# BUCK_CONVERTER_SCHEMAT_C.net
KiCad netlist of a schematic drawn in Altium Designer
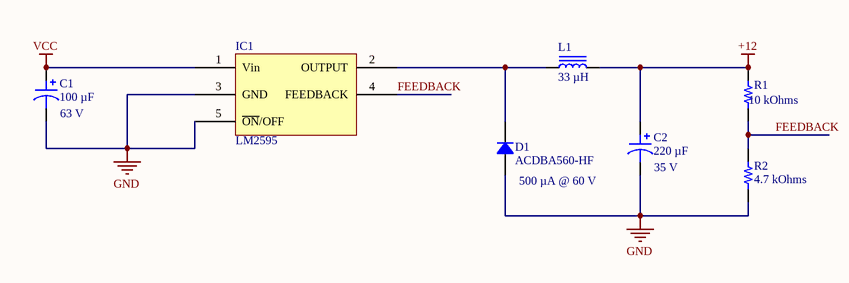
[diagram p0: BUCK CONVERTER SCHEMATİC.SchDoc]

(export (version "E")
  (design (tool "Eeschema 10.0.6"))
  (components
    (comp (ref "C1")
      (value "100 µF")
      (footprint "CAP AL TH D8 L3.5 H12.5")
      (description "CAP ALUM 100UF 20% 63V RADIAL")
      (fields
        (field (name "PART NUMBER") "ECA-1JM101")
        (field (name "MANUFACTURER") "Panasonic Electronic Components")
        (field (name "VOLTAGE - RATED") "63 V")
      )
      (libsource (lib "Celestial Altium Library - altium_library") (part "Polarised Capacitor"))
    )
    (comp (ref "C2")
      (value "220 µF")
      (footprint "CAP AL TH D8 L3.5 H12.5")
      (description "CAP ALUM 220UF 20% 35V RADIAL")
      (fields
        (field (name "PART NUMBER") "ECA-1VM221")
        (field (name "MANUFACTURER") "Panasonic Electronic Components")
        (field (name "VOLTAGE - RATED") "35 V")
      )
      (libsource (lib "Celestial Altium Library - altium_library") (part "Polarised Capacitor"))
    )
    (comp (ref "D1")
      (value "ACDBA560-HF")
      (footprint "DO214AC SMA")
      (description "DIODE SCHOTTKY 60V 5A DO214AC")
      (fields
        (field (name "CURRENT - REVERSE LEAKAGE @ VR") "500 µA @ 60 V")
        (field (name "MANUFACTURER") "Comchip Technology")
      )
      (libsource (lib "Celestial Altium Library - altium_library") (part "Diode"))
    )
    (comp (ref "IC1")
      (value "LM2595")
      (footprint "LM2596 FOOTPRİNT:LM2596 FOOTPRİNT")
      (libsource (lib "LM2595 SEMBOL") (part "LM2595"))
    )
    (comp (ref "L1")
      (value "33 µH")
      (footprint "BOURNS SRR1280")
      (description "FIXED IND 33UH 3.5A 57 MOHM SMD")
      (fields (field (name "PART NUMBER") "SRR1280-330M") (field (name "MANUFACTURER") "Bourns Inc."))
      (libsource (lib "Celestial Altium Library - altium_library") (part "Inductor"))
    )
    (comp (ref "R1")
      (value "10 kOhms")
      (footprint "RES 0805_2012")
      (description "RES 10K OHM 1% 1/3W 0805")
      (fields
        (field (name "PART NUMBER") "CRGP0805F10K")
        (field (name "MANUFACTURER") "TE Connectivity Passive Product")
      )
      (libsource (lib "Celestial Altium Library - altium_library") (part "Resistor"))
    )
    (comp (ref "R2")
      (value "4.7 kOhms")
      (footprint "RES 0805_2012")
      (description "RES 4.7K OHM 1% 1/3W 0805")
      (fields
        (field (name "PART NUMBER") "CRGP0805F4K7")
        (field (name "MANUFACTURER") "TE Connectivity Passive Product")
      )
      (libsource (lib "Celestial Altium Library - altium_library") (part "Resistor"))
    )
  )
  (nets
    (net (code "1") (name "+12") (class "Default")
      (node (ref "C2") (pin "1") (pinfunction "1_1") (pintype "passive"))
      (node (ref "L1") (pin "2") (pinfunction "2_2") (pintype "passive"))
      (node (ref "R1") (pin "2") (pinfunction "2_2") (pintype "passive"))
    )
    (net (code "2") (name "/FEEDBACK") (class "Default")
      (node (ref "IC1") (pin "4") (pinfunction "FEEDBACK_4") (pintype "passive"))
      (node (ref "R1") (pin "1") (pinfunction "1_1") (pintype "passive"))
      (node (ref "R2") (pin "2") (pinfunction "2_2") (pintype "passive"))
    )
    (net (code "3") (name "GND") (class "Default")
      (node (ref "C1") (pin "2") (pinfunction "2_2") (pintype "passive"))
      (node (ref "C2") (pin "2") (pinfunction "2_2") (pintype "passive"))
      (node (ref "D1") (pin "1") (pinfunction "1_1") (pintype "passive"))
      (node (ref "IC1") (pin "3") (pinfunction "GND_3") (pintype "passive"))
      (node (ref "IC1") (pin "5") (pinfunction "~{ON}/OFF_5") (pintype "passive"))
      (node (ref "R2") (pin "1") (pinfunction "1_1") (pintype "passive"))
    )
    (net (code "4") (name "Net-(IC1-OUTPUT)") (class "Default")
      (node (ref "D1") (pin "2") (pinfunction "2_2") (pintype "passive"))
      (node (ref "IC1") (pin "2") (pinfunction "OUTPUT_2") (pintype "passive"))
      (node (ref "L1") (pin "1") (pinfunction "1_1") (pintype "passive"))
    )
    (net (code "5") (name "VCC") (class "Default")
      (node (ref "C1") (pin "1") (pinfunction "1_1") (pintype "passive"))
      (node (ref "IC1") (pin "1") (pinfunction "Vin_1") (pintype "passive"))
    )
  )
)
